# RadioHTC_DISP.net
KiCad netlist of a schematic drawn in EAGLE
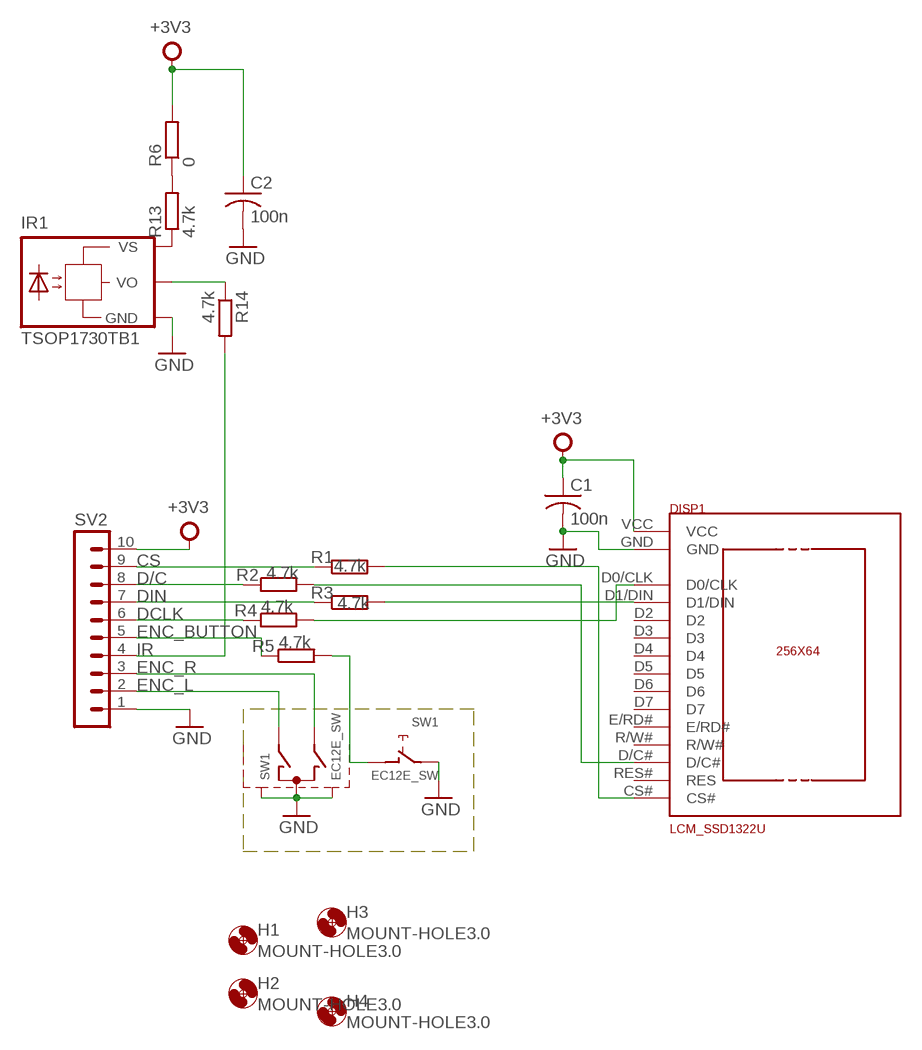
[diagram p0: schematic, sheet 1]

(export (version "E")
  (design (tool "Eeschema 10.0.6"))
  (components
    (comp (ref "C1")
      (value "100n")
      (footprint "eagle-import:C1206")
      (libsource (lib "eagle-import") (part "C-USC1206"))
    )
    (comp (ref "C2")
      (value "100n")
      (footprint "eagle-import:C1206")
      (libsource (lib "eagle-import") (part "C-USC1206"))
    )
    (comp (ref "DISP1")
      (value "LCM_SSD1322U")
      (footprint "eagle-import:LCM_SSD1322_VERT")
      (libsource (lib "eagle-import") (part "LCM_SSD1322U"))
    )
    (comp (ref "H1")
      (value "MOUNT-HOLE3.0")
      (footprint "eagle-import:3,0")
      (libsource (lib "eagle-import") (part "MOUNT-HOLE3.0"))
    )
    (comp (ref "H2")
      (value "MOUNT-HOLE3.0")
      (footprint "eagle-import:3,0")
      (libsource (lib "eagle-import") (part "MOUNT-HOLE3.0"))
    )
    (comp (ref "H3")
      (value "MOUNT-HOLE3.0")
      (footprint "eagle-import:3,0")
      (libsource (lib "eagle-import") (part "MOUNT-HOLE3.0"))
    )
    (comp (ref "H4")
      (value "MOUNT-HOLE3.0")
      (footprint "eagle-import:3,0")
      (libsource (lib "eagle-import") (part "MOUNT-HOLE3.0"))
    )
    (comp (ref "IR1")
      (value "TSOP1730TB1")
      (footprint "eagle-import:TSOP17_TB1")
      (libsource (lib "eagle-import") (part "TSOP17TB130"))
    )
    (comp (ref "R1")
      (value "4.7k")
      (footprint "eagle-import:R1206")
      (libsource (lib "eagle-import") (part "R-EU_R1206"))
    )
    (comp (ref "R2")
      (value "4.7k")
      (footprint "eagle-import:R1206")
      (libsource (lib "eagle-import") (part "R-EU_R1206"))
    )
    (comp (ref "R3")
      (value "4.7k")
      (footprint "eagle-import:R1206")
      (libsource (lib "eagle-import") (part "R-EU_R1206"))
    )
    (comp (ref "R4")
      (value "4.7k")
      (footprint "eagle-import:R1206")
      (libsource (lib "eagle-import") (part "R-EU_R1206"))
    )
    (comp (ref "R5")
      (value "4.7k")
      (footprint "eagle-import:R1206")
      (libsource (lib "eagle-import") (part "R-EU_R1206"))
    )
    (comp (ref "R6")
      (value "0")
      (footprint "eagle-import:R1206")
      (libsource (lib "eagle-import") (part "R-EU_R1206"))
    )
    (comp (ref "R13")
      (value "4.7k")
      (footprint "eagle-import:R1206")
      (libsource (lib "eagle-import") (part "R-EU_R1206"))
    )
    (comp (ref "R14")
      (value "4.7k")
      (footprint "eagle-import:R1206")
      (libsource (lib "eagle-import") (part "R-EU_R1206"))
    )
    (comp (ref "SV2")
      (value "MA10-1")
      (footprint "eagle-import:MA10-1")
      (libsource (lib "eagle-import") (part "MA10-1"))
    )
    (comp (ref "SW1")
      (value "EC12E_SW")
      (footprint "eagle-import:ALPS_EC12E_SW")
      (fields (field (name "MPN") "EC12E2424407"))
      (libsource (lib "eagle-import") (part "EC12E_SW"))
    )
  )
  (nets
    (net (code "1") (name "+3V3") (class "Default")
      (node (ref "C1") (pin "1") (pinfunction "1_1") (pintype "passive"))
      (node (ref "C2") (pin "1") (pinfunction "1_1") (pintype "passive"))
      (node (ref "DISP1") (pin "VCC") (pinfunction "VCC_VCC") (pintype "power_in"))
      (node (ref "R6") (pin "2") (pinfunction "2_2") (pintype "passive"))
      (node (ref "SV2") (pin "10") (pinfunction "10_10") (pintype "passive"))
    )
    (net (code "2") (name "/CS") (class "Default")
      (node (ref "R1") (pin "1") (pinfunction "1_1") (pintype "passive"))
      (node (ref "SV2") (pin "9") (pinfunction "9_9") (pintype "passive"))
    )
    (net (code "3") (name "/DCLK") (class "Default")
      (node (ref "R4") (pin "1") (pinfunction "1_1") (pintype "passive"))
      (node (ref "SV2") (pin "6") (pinfunction "6_6") (pintype "passive"))
    )
    (net (code "4") (name "/DIN") (class "Default")
      (node (ref "R3") (pin "1") (pinfunction "1_1") (pintype "passive"))
      (node (ref "SV2") (pin "7") (pinfunction "7_7") (pintype "passive"))
    )
    (net (code "5") (name "/D{slash}C") (class "Default")
      (node (ref "R2") (pin "1") (pinfunction "1_1") (pintype "passive"))
      (node (ref "SV2") (pin "8") (pinfunction "8_8") (pintype "passive"))
    )
    (net (code "6") (name "/ENC_BUTTON") (class "Default")
      (node (ref "R5") (pin "1") (pinfunction "1_1") (pintype "passive"))
      (node (ref "SV2") (pin "5") (pinfunction "5_5") (pintype "passive"))
    )
    (net (code "7") (name "/ENC_L") (class "Default")
      (node (ref "SV2") (pin "2") (pinfunction "2_2") (pintype "passive"))
      (node (ref "SW1") (pin "A") (pinfunction "A_A") (pintype "passive"))
    )
    (net (code "8") (name "/ENC_R") (class "Default")
      (node (ref "SV2") (pin "3") (pinfunction "3_3") (pintype "passive"))
      (node (ref "SW1") (pin "B") (pinfunction "B_B") (pintype "passive"))
    )
    (net (code "9") (name "/IR") (class "Default")
      (node (ref "R14") (pin "2") (pinfunction "2_2") (pintype "passive"))
      (node (ref "SV2") (pin "4") (pinfunction "4_4") (pintype "passive"))
    )
    (net (code "10") (name "GND") (class "Default")
      (node (ref "C1") (pin "2") (pinfunction "2_2") (pintype "passive"))
      (node (ref "C2") (pin "2") (pinfunction "2_2") (pintype "passive"))
      (node (ref "DISP1") (pin "GND") (pinfunction "GND_GND") (pintype "power_in"))
      (node (ref "IR1") (pin "GND") (pinfunction "GND_GND") (pintype "power_in"))
      (node (ref "SV2") (pin "1") (pinfunction "1_1") (pintype "passive"))
      (node (ref "SW1") (pin "C") (pinfunction "C_C") (pintype "passive"))
      (node (ref "SW1") (pin "E") (pinfunction "2_E") (pintype "passive"))
      (node (ref "SW1") (pin "GND@1") (pinfunction "P$2_GND@1") (pintype "power_in"))
      (node (ref "SW1") (pin "GND@2") (pinfunction "P$1_GND@2") (pintype "power_in"))
    )
    (net (code "11") (name "Net-(DISP1-PadCS#)") (class "Default")
      (node (ref "DISP1") (pin "CS#") (pinfunction "CS#_CS#") (pintype "input"))
      (node (ref "R1") (pin "2") (pinfunction "2_2") (pintype "passive"))
    )
    (net (code "12") (name "Net-(DISP1-PadD0{slash}CLK)") (class "Default")
      (node (ref "DISP1") (pin "D0/CLK") (pinfunction "D0/CLK_D0/CLK") (pintype "input"))
      (node (ref "R4") (pin "2") (pinfunction "2_2") (pintype "passive"))
    )
    (net (code "13") (name "Net-(DISP1-PadD1{slash}DIN)") (class "Default")
      (node (ref "DISP1") (pin "D1/DIN") (pinfunction "D1/DIN_D1/DIN") (pintype "input"))
      (node (ref "R3") (pin "2") (pinfunction "2_2") (pintype "passive"))
    )
    (net (code "14") (name "Net-(DISP1-PadD{slash}C#)") (class "Default")
      (node (ref "DISP1") (pin "D/C#") (pinfunction "D/C#_D/C#") (pintype "input"))
      (node (ref "R2") (pin "2") (pinfunction "2_2") (pintype "passive"))
    )
    (net (code "15") (name "Net-(IR1-PadVO)") (class "Default")
      (node (ref "IR1") (pin "VO") (pinfunction "VO_VO") (pintype "open_collector"))
      (node (ref "R14") (pin "1") (pinfunction "1_1") (pintype "passive"))
    )
    (net (code "16") (name "Net-(IR1-PadVS)") (class "Default")
      (node (ref "IR1") (pin "VS") (pinfunction "VS_VS") (pintype "power_in"))
      (node (ref "R13") (pin "1") (pinfunction "1_1") (pintype "passive"))
    )
    (net (code "17") (name "Net-(R13-Pad2)") (class "Default")
      (node (ref "R13") (pin "2") (pinfunction "2_2") (pintype "passive"))
      (node (ref "R6") (pin "1") (pinfunction "1_1") (pintype "passive"))
    )
    (net (code "18") (name "Net-(SW1B-1)") (class "Default")
      (node (ref "R5") (pin "2") (pinfunction "2_2") (pintype "passive"))
      (node (ref "SW1") (pin "D") (pinfunction "1_D") (pintype "passive"))
    )
    (net (code "19") (name "unconnected-(DISP1-PadD2)") (class "Default")
      (node (ref "DISP1") (pin "D2") (pinfunction "D2_D2") (pintype "input"))
    )
    (net (code "20") (name "unconnected-(DISP1-PadD3)") (class "Default")
      (node (ref "DISP1") (pin "D3") (pinfunction "D3_D3") (pintype "input"))
    )
    (net (code "21") (name "unconnected-(DISP1-PadD4)") (class "Default")
      (node (ref "DISP1") (pin "D4") (pinfunction "D4_D4") (pintype "input"))
    )
    (net (code "22") (name "unconnected-(DISP1-PadD5)") (class "Default")
      (node (ref "DISP1") (pin "D5") (pinfunction "D5_D5") (pintype "input"))
    )
    (net (code "23") (name "unconnected-(DISP1-PadD6)") (class "Default")
      (node (ref "DISP1") (pin "D6") (pinfunction "D6_D6") (pintype "input"))
    )
    (net (code "24") (name "unconnected-(DISP1-PadD7)") (class "Default")
      (node (ref "DISP1") (pin "D7") (pinfunction "D7_D7") (pintype "input"))
    )
    (net (code "25") (name "unconnected-(DISP1-PadE{slash}RD#)") (class "Default")
      (node (ref "DISP1") (pin "E/RD#") (pinfunction "E/RD#_E/RD#") (pintype "input"))
    )
    (net (code "26") (name "unconnected-(DISP1-PadR{slash}W#)") (class "Default")
      (node (ref "DISP1") (pin "R/W#") (pinfunction "R/W#_R/W#") (pintype "input"))
    )
    (net (code "27") (name "unconnected-(DISP1-RES-PadRES#)") (class "Default")
      (node (ref "DISP1") (pin "RES#") (pinfunction "RES_RES#") (pintype "input"))
    )
  )
)
